# POW_Schematic3.net
KiCad netlist of a schematic drawn in Altium Designer
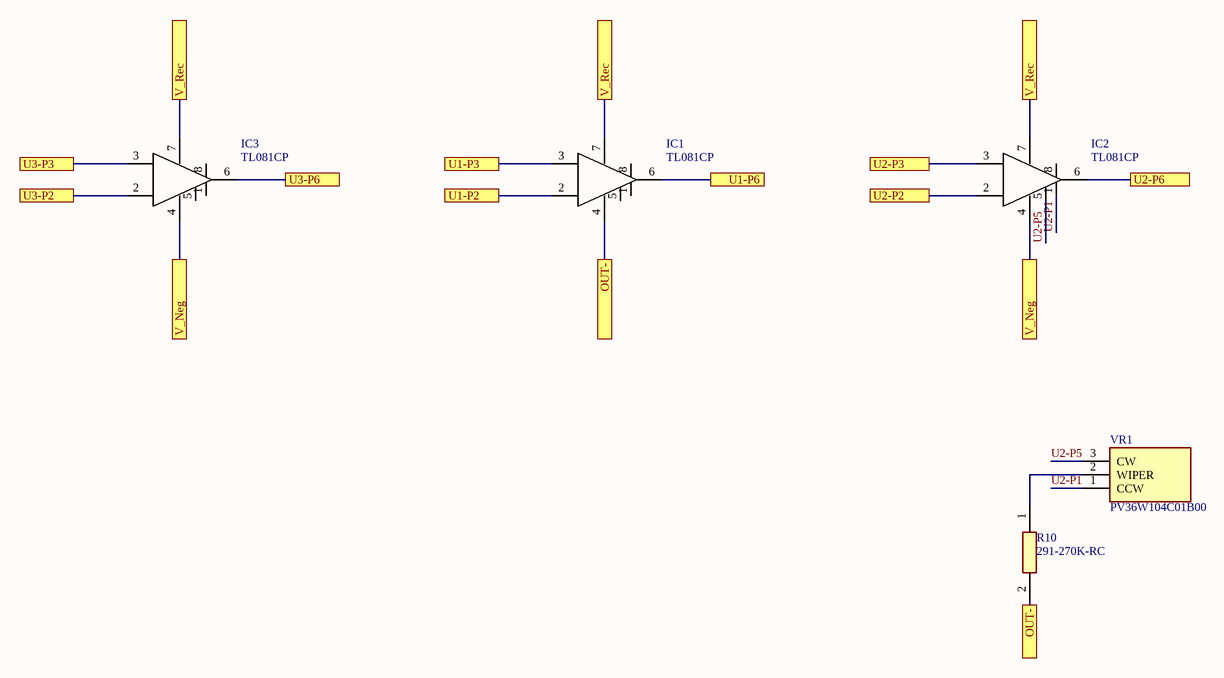
[diagram p0: POW_Schematic3.SchDoc]

(export (version "E")
  (design (tool "Eeschema 10.0.6"))
  (components
    (comp (ref "IC1")
      (value "TL081CP")
      (footprint "DIP794W53P254L959H508Q8N")
      (description "Integrated Circuit")
      (fields (field (name "MOUSER PART NUMBER") "595-TL081CP") (field (name "RS PART NUMBER") "0304223P"))
      (libsource (lib "Schlib_POW_HugoHamblok") (part "TL081CP"))
    )
    (comp (ref "IC2")
      (value "TL081CP")
      (footprint "DIP794W53P254L959H508Q8N")
      (description "Integrated Circuit")
      (fields (field (name "MOUSER PART NUMBER") "595-TL081CP") (field (name "RS PART NUMBER") "0304223P"))
      (libsource (lib "Schlib_POW_HugoHamblok") (part "TL081CP"))
    )
    (comp (ref "IC3")
      (value "TL081CP")
      (footprint "DIP794W53P254L959H508Q8N")
      (description "Integrated Circuit")
      (fields (field (name "MOUSER PART NUMBER") "595-TL081CP") (field (name "RS PART NUMBER") "0304223P"))
      (libsource (lib "Schlib_POW_HugoHamblok") (part "TL081CP"))
    )
    (comp (ref "R10")
      (value "291-270K-RC")
      (footprint "291-XXX-RC-Type")
      (libsource (lib "Schlib_POW_HugoHamblok") (part "291-270K-RC"))
    )
    (comp (ref "VR1")
      (value "PV36W104C01B00")
      (footprint "PV36W")
      (description "Variable Resistor")
      (fields
        (field (name "MOUSER PART NUMBER") "81-PV36W104C01B00")
        (field (name "RS PART NUMBER") "7692160P")
      )
      (libsource (lib "Schlib_POW_HugoHamblok") (part "PV36W104C01B00"))
    )
  )
  (nets
    (net (code "1") (name "/OUT-") (class "Default")
      (node (ref "IC1") (pin "4") (pintype "passive"))
      (node (ref "R10") (pin "2") (pinfunction "2_2") (pintype "passive"))
    )
    (net (code "2") (name "/U1-P2") (class "Default") (node (ref "IC1") (pin "2") (pintype "passive")))
    (net (code "3") (name "/U1-P3") (class "Default") (node (ref "IC1") (pin "3") (pintype "passive")))
    (net (code "4") (name "/U1-P6") (class "Default") (node (ref "IC1") (pin "6") (pintype "passive")))
    (net (code "5") (name "/U2-P1") (class "Default")
      (node (ref "IC2") (pin "1") (pintype "passive"))
      (node (ref "VR1") (pin "1") (pinfunction "CCW_1") (pintype "passive"))
    )
    (net (code "6") (name "/U2-P2") (class "Default") (node (ref "IC2") (pin "2") (pintype "passive")))
    (net (code "7") (name "/U2-P3") (class "Default") (node (ref "IC2") (pin "3") (pintype "passive")))
    (net (code "8") (name "/U2-P5") (class "Default")
      (node (ref "IC2") (pin "5") (pintype "passive"))
      (node (ref "VR1") (pin "3") (pinfunction "CW_3") (pintype "passive"))
    )
    (net (code "9") (name "/U2-P6") (class "Default") (node (ref "IC2") (pin "6") (pintype "passive")))
    (net (code "10") (name "/U3-P2") (class "Default") (node (ref "IC3") (pin "2") (pintype "passive")))
    (net (code "11") (name "/U3-P3") (class "Default") (node (ref "IC3") (pin "3") (pintype "passive")))
    (net (code "12") (name "/U3-P6") (class "Default") (node (ref "IC3") (pin "6") (pintype "passive")))
    (net (code "13") (name "/V_Neg") (class "Default")
      (node (ref "IC2") (pin "4") (pintype "passive"))
      (node (ref "IC3") (pin "4") (pintype "passive"))
    )
    (net (code "14") (name "/V_Rec") (class "Default")
      (node (ref "IC1") (pin "7") (pintype "passive"))
      (node (ref "IC2") (pin "7") (pintype "passive"))
      (node (ref "IC3") (pin "7") (pintype "passive"))
    )
    (net (code "15") (name "Net-(VR1-WIPER)") (class "Default")
      (node (ref "R10") (pin "1") (pinfunction "1_1") (pintype "passive"))
      (node (ref "VR1") (pin "2") (pinfunction "WIPER_2") (pintype "passive"))
    )
    (net (code "16") (name "unconnected-(IC1-Pad1)") (class "Default")
      (node (ref "IC1") (pin "1") (pintype "passive"))
    )
    (net (code "17") (name "unconnected-(IC1-Pad5)") (class "Default")
      (node (ref "IC1") (pin "5") (pintype "passive"))
    )
    (net (code "18") (name "unconnected-(IC1-Pad8)") (class "Default")
      (node (ref "IC1") (pin "8") (pintype "passive"))
    )
    (net (code "19") (name "unconnected-(IC2-Pad8)") (class "Default")
      (node (ref "IC2") (pin "8") (pintype "passive"))
    )
    (net (code "20") (name "unconnected-(IC3-Pad1)") (class "Default")
      (node (ref "IC3") (pin "1") (pintype "passive"))
    )
    (net (code "21") (name "unconnected-(IC3-Pad5)") (class "Default")
      (node (ref "IC3") (pin "5") (pintype "passive"))
    )
    (net (code "22") (name "unconnected-(IC3-Pad8)") (class "Default")
      (node (ref "IC3") (pin "8") (pintype "passive"))
    )
  )
)
